# lfovca-rev3.net
KiCad netlist of a schematic drawn in EAGLE
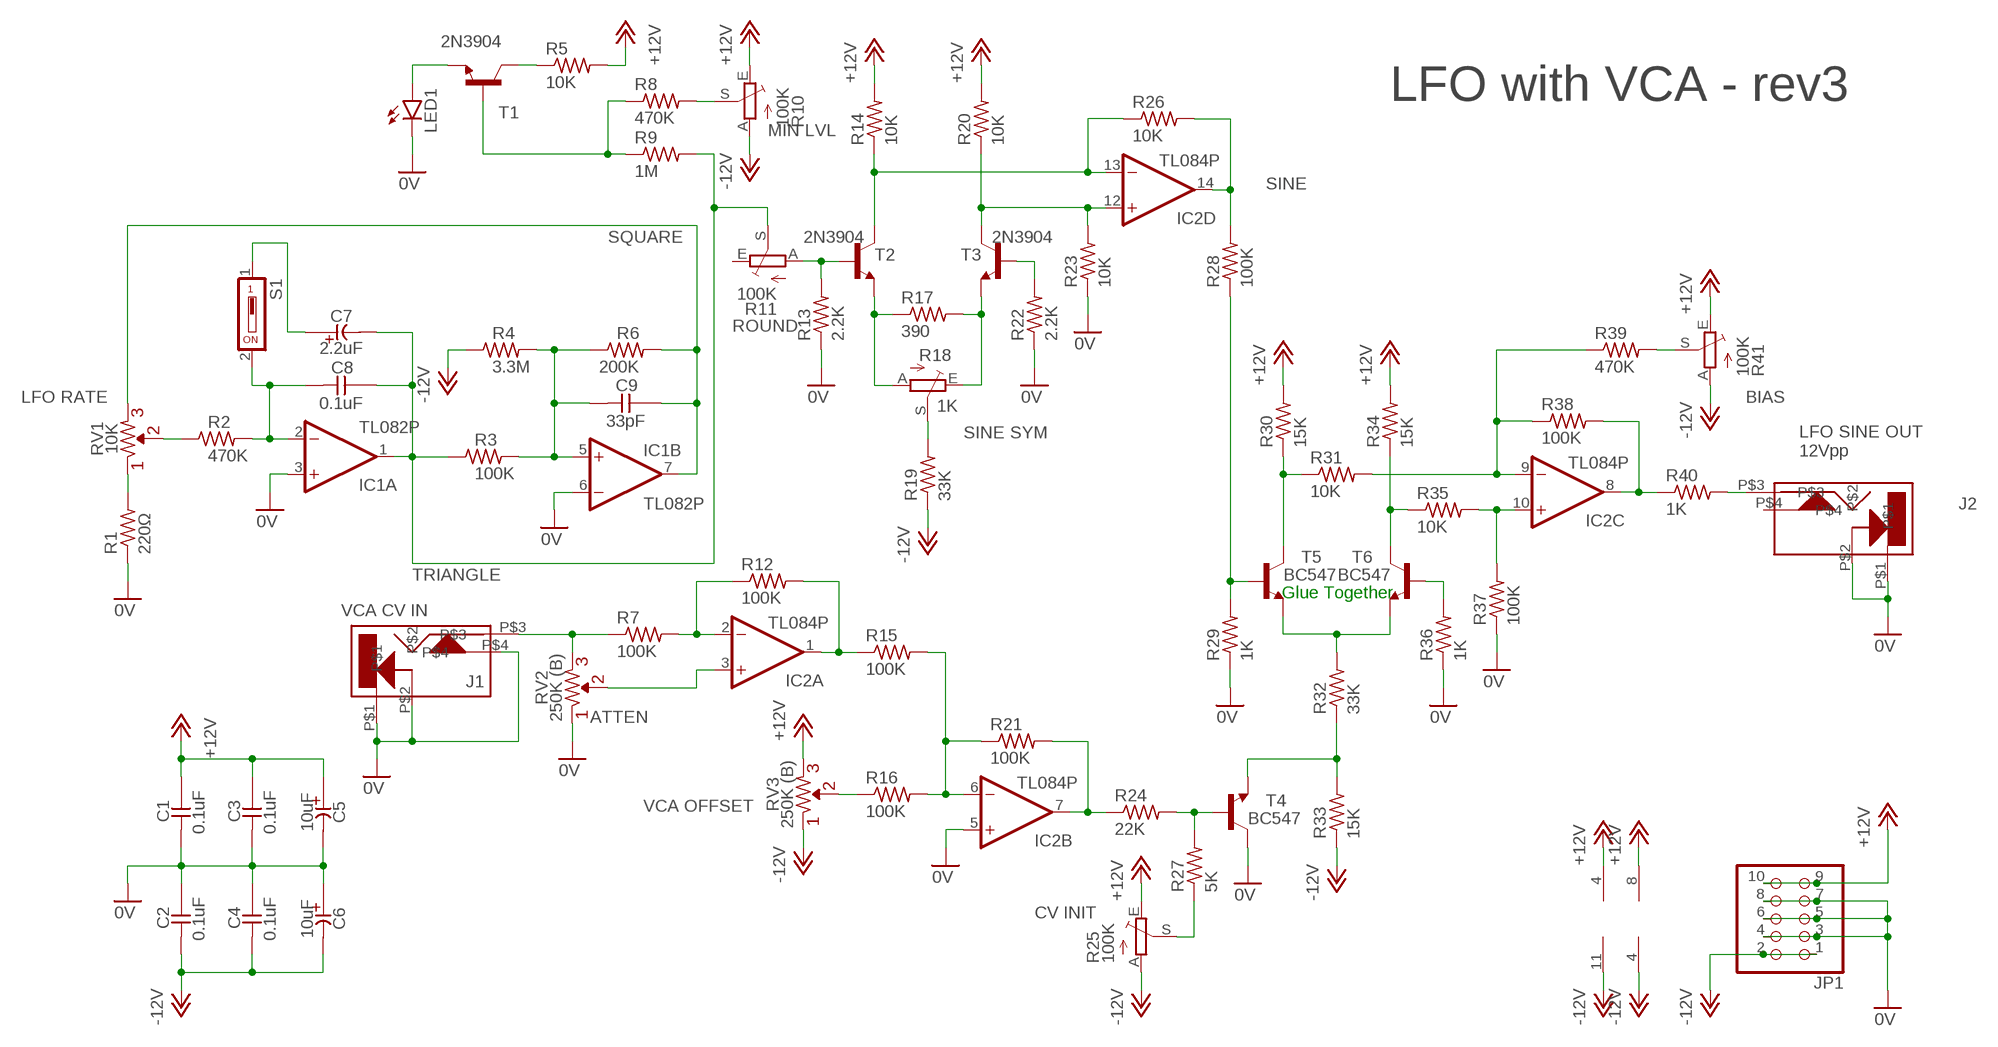
[diagram p0: schematic, sheet 1]

(export (version "E")
  (design (tool "Eeschema 10.0.6"))
  (components
    (comp (ref "C1")
      (value "0.1uF")
      (footprint "eagle-import:C025-024X044")
      (libsource (lib "eagle-import") (part "CC-US025-024X044"))
    )
    (comp (ref "C2")
      (value "0.1uF")
      (footprint "eagle-import:C025-024X044")
      (libsource (lib "eagle-import") (part "CC-US025-024X044"))
    )
    (comp (ref "C3")
      (value "0.1uF")
      (footprint "eagle-import:C025-024X044")
      (libsource (lib "eagle-import") (part "CC-US025-024X044"))
    )
    (comp (ref "C4")
      (value "0.1uF")
      (footprint "eagle-import:C025-024X044")
      (libsource (lib "eagle-import") (part "CC-US025-024X044"))
    )
    (comp (ref "C5")
      (value "10uF")
      (footprint "eagle-import:E2-5")
      (libsource (lib "eagle-import") (part "CE-USE2-5"))
    )
    (comp (ref "C6")
      (value "10uF")
      (footprint "eagle-import:E2-5")
      (libsource (lib "eagle-import") (part "CE-USE2-5"))
    )
    (comp (ref "C7")
      (value "2.2uF")
      (footprint "eagle-import:E2-5")
      (libsource (lib "eagle-import") (part "CE-USE2-5"))
    )
    (comp (ref "C8")
      (value "0.1uF")
      (footprint "eagle-import:C025-024X044")
      (libsource (lib "eagle-import") (part "CC-US025-024X044"))
    )
    (comp (ref "C9")
      (value "33pF")
      (footprint "eagle-import:C025-024X044")
      (libsource (lib "eagle-import") (part "CC-US025-024X044"))
    )
    (comp (ref "IC1")
      (value "TL082P")
      (footprint "eagle-import:DIL08")
      (libsource (lib "eagle-import") (part "TL082P"))
    )
    (comp (ref "IC2")
      (value "TL084P")
      (footprint "eagle-import:DIL14")
      (libsource (lib "eagle-import") (part "TL084P"))
    )
    (comp (ref "J1")
      (value "CL1384")
      (footprint "eagle-import:CL1384")
      (libsource (lib "eagle-import") (part "CL1384"))
    )
    (comp (ref "J2")
      (value "CL1384")
      (footprint "eagle-import:CL1384")
      (libsource (lib "eagle-import") (part "CL1384"))
    )
    (comp (ref "JP1")
      (value "PINHD-2X5")
      (footprint "eagle-import:2X05")
      (libsource (lib "eagle-import") (part "PINHD-2X5"))
    )
    (comp (ref "LED1")
      (value "LED3MM")
      (footprint "eagle-import:LED3MM")
      (libsource (lib "eagle-import") (part "LED3MM"))
    )
    (comp (ref "R1")
      (value "220Ω")
      (footprint "eagle-import:0207_7")
      (libsource (lib "eagle-import") (part "R-US_0207/7"))
    )
    (comp (ref "R2")
      (value "470K")
      (footprint "eagle-import:0207_7")
      (libsource (lib "eagle-import") (part "R-US_0207/7"))
    )
    (comp (ref "R3")
      (value "100K")
      (footprint "eagle-import:0207_7")
      (libsource (lib "eagle-import") (part "R-US_0207/7"))
    )
    (comp (ref "R4")
      (value "3.3M")
      (footprint "eagle-import:0207_7")
      (libsource (lib "eagle-import") (part "R-US_0207/7"))
    )
    (comp (ref "R5")
      (value "10K")
      (footprint "eagle-import:0207_7")
      (libsource (lib "eagle-import") (part "R-US_0207/7"))
    )
    (comp (ref "R6")
      (value "200K")
      (footprint "eagle-import:0207_7")
      (libsource (lib "eagle-import") (part "R-US_0207/7"))
    )
    (comp (ref "R7")
      (value "100K")
      (footprint "eagle-import:0207_7")
      (libsource (lib "eagle-import") (part "R-US_0207/7"))
    )
    (comp (ref "R8")
      (value "470K")
      (footprint "eagle-import:0207_7")
      (libsource (lib "eagle-import") (part "R-US_0207/7"))
    )
    (comp (ref "R9")
      (value "1M")
      (footprint "eagle-import:0207_7")
      (libsource (lib "eagle-import") (part "R-US_0207/7"))
    )
    (comp (ref "R10")
      (value "100K")
      (footprint "eagle-import:CA6V")
      (libsource (lib "eagle-import") (part "TRIM_EU-CA6V"))
    )
    (comp (ref "R11")
      (value "100K")
      (footprint "eagle-import:CA6V")
      (libsource (lib "eagle-import") (part "TRIM_EU-CA6V"))
    )
    (comp (ref "R12")
      (value "100K")
      (footprint "eagle-import:0207_7")
      (libsource (lib "eagle-import") (part "R-US_0207/7"))
    )
    (comp (ref "R13")
      (value "2.2K")
      (footprint "eagle-import:0207_7")
      (libsource (lib "eagle-import") (part "R-US_0207/7"))
    )
    (comp (ref "R14")
      (value "10K")
      (footprint "eagle-import:0207_7")
      (libsource (lib "eagle-import") (part "R-US_0207/7"))
    )
    (comp (ref "R15")
      (value "100K")
      (footprint "eagle-import:0207_7")
      (libsource (lib "eagle-import") (part "R-US_0207/7"))
    )
    (comp (ref "R16")
      (value "100K")
      (footprint "eagle-import:0207_7")
      (libsource (lib "eagle-import") (part "R-US_0207/7"))
    )
    (comp (ref "R17")
      (value "390")
      (footprint "eagle-import:0207_7")
      (libsource (lib "eagle-import") (part "R-US_0207/7"))
    )
    (comp (ref "R18")
      (value "1K")
      (footprint "eagle-import:CA6V")
      (libsource (lib "eagle-import") (part "TRIM_EU-CA6V"))
    )
    (comp (ref "R19")
      (value "33K")
      (footprint "eagle-import:0207_7")
      (libsource (lib "eagle-import") (part "R-US_0207/7"))
    )
    (comp (ref "R20")
      (value "10K")
      (footprint "eagle-import:0207_7")
      (libsource (lib "eagle-import") (part "R-US_0207/7"))
    )
    (comp (ref "R21")
      (value "100K")
      (footprint "eagle-import:0207_7")
      (libsource (lib "eagle-import") (part "R-US_0207/7"))
    )
    (comp (ref "R22")
      (value "2.2K")
      (footprint "eagle-import:0207_7")
      (libsource (lib "eagle-import") (part "R-US_0207/7"))
    )
    (comp (ref "R23")
      (value "10K")
      (footprint "eagle-import:0207_7")
      (libsource (lib "eagle-import") (part "R-US_0207/7"))
    )
    (comp (ref "R24")
      (value "22K")
      (footprint "eagle-import:0207_7")
      (libsource (lib "eagle-import") (part "R-US_0207/7"))
    )
    (comp (ref "R25")
      (value "100K")
      (footprint "eagle-import:CA6V")
      (libsource (lib "eagle-import") (part "TRIM_EU-CA6V"))
    )
    (comp (ref "R26")
      (value "10K")
      (footprint "eagle-import:0207_7")
      (libsource (lib "eagle-import") (part "R-US_0207/7"))
    )
    (comp (ref "R27")
      (value "5K")
      (footprint "eagle-import:0207_7")
      (libsource (lib "eagle-import") (part "R-US_0207/7"))
    )
    (comp (ref "R28")
      (value "100K")
      (footprint "eagle-import:0207_7")
      (libsource (lib "eagle-import") (part "R-US_0207/7"))
    )
    (comp (ref "R29")
      (value "1K")
      (footprint "eagle-import:0207_7")
      (libsource (lib "eagle-import") (part "R-US_0207/7"))
    )
    (comp (ref "R30")
      (value "15K")
      (footprint "eagle-import:0207_7")
      (libsource (lib "eagle-import") (part "R-US_0207/7"))
    )
    (comp (ref "R31")
      (value "10K")
      (footprint "eagle-import:0207_7")
      (libsource (lib "eagle-import") (part "R-US_0207/7"))
    )
    (comp (ref "R32")
      (value "33K")
      (footprint "eagle-import:0207_7")
      (libsource (lib "eagle-import") (part "R-US_0207/7"))
    )
    (comp (ref "R33")
      (value "15K")
      (footprint "eagle-import:0207_7")
      (libsource (lib "eagle-import") (part "R-US_0207/7"))
    )
    (comp (ref "R34")
      (value "15K")
      (footprint "eagle-import:0207_7")
      (libsource (lib "eagle-import") (part "R-US_0207/7"))
    )
    (comp (ref "R35")
      (value "10K")
      (footprint "eagle-import:0207_7")
      (libsource (lib "eagle-import") (part "R-US_0207/7"))
    )
    (comp (ref "R36")
      (value "1K")
      (footprint "eagle-import:0207_7")
      (libsource (lib "eagle-import") (part "R-US_0207/7"))
    )
    (comp (ref "R37")
      (value "100K")
      (footprint "eagle-import:0207_7")
      (libsource (lib "eagle-import") (part "R-US_0207/7"))
    )
    (comp (ref "R38")
      (value "100K")
      (footprint "eagle-import:0207_7")
      (libsource (lib "eagle-import") (part "R-US_0207/7"))
    )
    (comp (ref "R39")
      (value "470K")
      (footprint "eagle-import:0207_7")
      (libsource (lib "eagle-import") (part "R-US_0207/7"))
    )
    (comp (ref "R40")
      (value "1K")
      (footprint "eagle-import:0207_7")
      (libsource (lib "eagle-import") (part "R-US_0207/7"))
    )
    (comp (ref "R41")
      (value "100K")
      (footprint "eagle-import:CA6V")
      (libsource (lib "eagle-import") (part "TRIM_EU-CA6V"))
    )
    (comp (ref "RV1")
      (value "10K")
      (footprint "eagle-import:_COMMON_3RP_1610N")
      (libsource (lib "eagle-import") (part "R-VARR-VAR-10"))
    )
    (comp (ref "RV2")
      (value "250K (B)")
      (footprint "eagle-import:_COMMON_3RP_1610N")
      (libsource (lib "eagle-import") (part "R-VARR-VAR-10"))
    )
    (comp (ref "RV3")
      (value "250K (B)")
      (footprint "eagle-import:_COMMON_3RP_1610N")
      (libsource (lib "eagle-import") (part "R-VARR-VAR-10"))
    )
    (comp (ref "S1")
      (value "DS01")
      (footprint "eagle-import:DS-01")
      (libsource (lib "eagle-import") (part "DS01"))
    )
    (comp (ref "T1")
      (value "2N3904")
      (footprint "eagle-import:TO92-EBC")
      (libsource (lib "eagle-import") (part "-NPN-TO92-EBC2N3904"))
    )
    (comp (ref "T2")
      (value "2N3904")
      (footprint "eagle-import:TO92-EBC")
      (libsource (lib "eagle-import") (part "-NPN-TO92-EBC2N3904"))
    )
    (comp (ref "T3")
      (value "2N3904")
      (footprint "eagle-import:TO92-EBC")
      (libsource (lib "eagle-import") (part "-NPN-TO92-EBC2N3904"))
    )
    (comp (ref "T4")
      (value "BC547")
      (footprint "eagle-import:TO92-CBE")
      (libsource (lib "eagle-import") (part "-NPN-TO92-CBEBC547"))
    )
    (comp (ref "T5")
      (value "BC547")
      (footprint "eagle-import:TO92-CBE")
      (libsource (lib "eagle-import") (part "-NPN-TO92-CBEBC547"))
    )
    (comp (ref "T6")
      (value "BC547")
      (footprint "eagle-import:TO92-CBE")
      (libsource (lib "eagle-import") (part "-NPN-TO92-CBEBC547"))
    )
  )
  (nets
    (net (code "1") (name "+12V") (class "Default")
      (node (ref "C1") (pin "1") (pinfunction "1_1") (pintype "passive"))
      (node (ref "C3") (pin "1") (pinfunction "1_1") (pintype "passive"))
      (node (ref "C5") (pin "+") (pinfunction "+_+") (pintype "passive"))
      (node (ref "IC1") (pin "8") (pinfunction "V+_8") (pintype "power_in"))
      (node (ref "IC2") (pin "4") (pinfunction "V+_4") (pintype "power_in"))
      (node (ref "JP1") (pin "10") (pinfunction "10_10") (pintype "passive"))
      (node (ref "JP1") (pin "9") (pinfunction "9_9") (pintype "passive"))
      (node (ref "R10") (pin "E") (pinfunction "E_E") (pintype "passive"))
      (node (ref "R14") (pin "2") (pinfunction "2_2") (pintype "passive"))
      (node (ref "R20") (pin "2") (pinfunction "2_2") (pintype "passive"))
      (node (ref "R25") (pin "E") (pinfunction "E_E") (pintype "passive"))
      (node (ref "R30") (pin "2") (pinfunction "2_2") (pintype "passive"))
      (node (ref "R34") (pin "2") (pinfunction "2_2") (pintype "passive"))
      (node (ref "R41") (pin "E") (pinfunction "E_E") (pintype "passive"))
      (node (ref "R5") (pin "2") (pinfunction "2_2") (pintype "passive"))
      (node (ref "RV3") (pin "3") (pinfunction "3_3") (pintype "passive"))
    )
    (net (code "2") (name "-12V") (class "Default")
      (node (ref "C2") (pin "2") (pinfunction "2_2") (pintype "passive"))
      (node (ref "C4") (pin "2") (pinfunction "2_2") (pintype "passive"))
      (node (ref "C6") (pin "-") (pinfunction "-_-") (pintype "passive"))
      (node (ref "IC1") (pin "4") (pinfunction "V-_4") (pintype "power_in"))
      (node (ref "IC2") (pin "11") (pinfunction "V-_11") (pintype "power_in"))
      (node (ref "JP1") (pin "1") (pinfunction "1_1") (pintype "passive"))
      (node (ref "JP1") (pin "2") (pinfunction "2_2") (pintype "passive"))
      (node (ref "R10") (pin "A") (pinfunction "A_A") (pintype "passive"))
      (node (ref "R19") (pin "1") (pinfunction "1_1") (pintype "passive"))
      (node (ref "R25") (pin "A") (pinfunction "A_A") (pintype "passive"))
      (node (ref "R33") (pin "1") (pinfunction "1_1") (pintype "passive"))
      (node (ref "R4") (pin "1") (pinfunction "1_1") (pintype "passive"))
      (node (ref "R41") (pin "A") (pinfunction "A_A") (pintype "passive"))
      (node (ref "RV3") (pin "1") (pinfunction "1_1") (pintype "passive"))
    )
    (net (code "3") (name "0V") (class "Default")
      (node (ref "C1") (pin "2") (pinfunction "2_2") (pintype "passive"))
      (node (ref "C2") (pin "1") (pinfunction "1_1") (pintype "passive"))
      (node (ref "C3") (pin "2") (pinfunction "2_2") (pintype "passive"))
      (node (ref "C4") (pin "1") (pinfunction "1_1") (pintype "passive"))
      (node (ref "C5") (pin "-") (pinfunction "-_-") (pintype "passive"))
      (node (ref "C6") (pin "+") (pinfunction "+_+") (pintype "passive"))
      (node (ref "IC1") (pin "3") (pinfunction "+IN_3") (pintype "input"))
      (node (ref "IC1") (pin "6") (pinfunction "-IN_6") (pintype "input"))
      (node (ref "IC2") (pin "5") (pinfunction "+IN_5") (pintype "input"))
      (node (ref "J1") (pin "P$1") (pinfunction "P$1_P$1") (pintype "bidirectional"))
      (node (ref "J1") (pin "P$2") (pinfunction "P$2_P$2") (pintype "bidirectional"))
      (node (ref "J1") (pin "P$4") (pinfunction "P$4_P$4") (pintype "bidirectional"))
      (node (ref "J2") (pin "P$1") (pinfunction "P$1_P$1") (pintype "bidirectional"))
      (node (ref "J2") (pin "P$2") (pinfunction "P$2_P$2") (pintype "bidirectional"))
      (node (ref "JP1") (pin "3") (pinfunction "3_3") (pintype "passive"))
      (node (ref "JP1") (pin "4") (pinfunction "4_4") (pintype "passive"))
      (node (ref "JP1") (pin "5") (pinfunction "5_5") (pintype "passive"))
      (node (ref "JP1") (pin "6") (pinfunction "6_6") (pintype "passive"))
      (node (ref "JP1") (pin "7") (pinfunction "7_7") (pintype "passive"))
      (node (ref "JP1") (pin "8") (pinfunction "8_8") (pintype "passive"))
      (node (ref "LED1") (pin "K") (pinfunction "C_K") (pintype "passive"))
      (node (ref "R1") (pin "1") (pinfunction "1_1") (pintype "passive"))
      (node (ref "R13") (pin "1") (pinfunction "1_1") (pintype "passive"))
      (node (ref "R22") (pin "1") (pinfunction "1_1") (pintype "passive"))
      (node (ref "R23") (pin "1") (pinfunction "1_1") (pintype "passive"))
      (node (ref "R29") (pin "1") (pinfunction "1_1") (pintype "passive"))
      (node (ref "R36") (pin "1") (pinfunction "1_1") (pintype "passive"))
      (node (ref "R37") (pin "1") (pinfunction "1_1") (pintype "passive"))
      (node (ref "RV2") (pin "1") (pinfunction "1_1") (pintype "passive"))
      (node (ref "T4") (pin "C") (pinfunction "C_C") (pintype "passive"))
    )
    (net (code "4") (name "Net-(C7-Pad+)") (class "Default")
      (node (ref "C7") (pin "+") (pinfunction "+_+") (pintype "passive"))
      (node (ref "S1") (pin "1") (pinfunction "1_1") (pintype "passive"))
    )
    (net (code "5") (name "Net-(IC1A--IN)") (class "Default")
      (node (ref "C8") (pin "2") (pinfunction "2_2") (pintype "passive"))
      (node (ref "IC1") (pin "2") (pinfunction "-IN_2") (pintype "input"))
      (node (ref "R2") (pin "2") (pinfunction "2_2") (pintype "passive"))
      (node (ref "S1") (pin "2") (pinfunction "2_2") (pintype "passive"))
    )
    (net (code "6") (name "Net-(IC1A-OUT)") (class "Default")
      (node (ref "C7") (pin "-") (pinfunction "-_-") (pintype "passive"))
      (node (ref "C8") (pin "1") (pinfunction "1_1") (pintype "passive"))
      (node (ref "IC1") (pin "1") (pinfunction "OUT_1") (pintype "output"))
      (node (ref "R11") (pin "S") (pinfunction "S_S") (pintype "passive"))
      (node (ref "R3") (pin "1") (pinfunction "1_1") (pintype "passive"))
      (node (ref "R9") (pin "2") (pinfunction "2_2") (pintype "passive"))
    )
    (net (code "7") (name "Net-(IC1B-+IN)") (class "Default")
      (node (ref "C9") (pin "2") (pinfunction "2_2") (pintype "passive"))
      (node (ref "IC1") (pin "5") (pinfunction "+IN_5") (pintype "input"))
      (node (ref "R3") (pin "2") (pinfunction "2_2") (pintype "passive"))
      (node (ref "R4") (pin "2") (pinfunction "2_2") (pintype "passive"))
      (node (ref "R6") (pin "1") (pinfunction "1_1") (pintype "passive"))
    )
    (net (code "8") (name "Net-(IC1B-OUT)") (class "Default")
      (node (ref "C9") (pin "1") (pinfunction "1_1") (pintype "passive"))
      (node (ref "IC1") (pin "7") (pinfunction "OUT_7") (pintype "output"))
      (node (ref "R6") (pin "2") (pinfunction "2_2") (pintype "passive"))
      (node (ref "RV1") (pin "3") (pinfunction "3_3") (pintype "passive"))
    )
    (net (code "9") (name "Net-(IC2A-+IN)") (class "Default")
      (node (ref "IC2") (pin "3") (pinfunction "+IN_3") (pintype "input"))
      (node (ref "RV2") (pin "2") (pinfunction "2_2") (pintype "passive"))
    )
    (net (code "10") (name "Net-(IC2A--IN)") (class "Default")
      (node (ref "IC2") (pin "2") (pinfunction "-IN_2") (pintype "input"))
      (node (ref "R12") (pin "1") (pinfunction "1_1") (pintype "passive"))
      (node (ref "R7") (pin "2") (pinfunction "2_2") (pintype "passive"))
    )
    (net (code "11") (name "Net-(IC2A-OUT)") (class "Default")
      (node (ref "IC2") (pin "1") (pinfunction "OUT_1") (pintype "output"))
      (node (ref "R12") (pin "2") (pinfunction "2_2") (pintype "passive"))
      (node (ref "R15") (pin "1") (pinfunction "1_1") (pintype "passive"))
    )
    (net (code "12") (name "Net-(IC2B--IN)") (class "Default")
      (node (ref "IC2") (pin "6") (pinfunction "-IN_6") (pintype "input"))
      (node (ref "R15") (pin "2") (pinfunction "2_2") (pintype "passive"))
      (node (ref "R16") (pin "2") (pinfunction "2_2") (pintype "passive"))
      (node (ref "R21") (pin "1") (pinfunction "1_1") (pintype "passive"))
    )
    (net (code "13") (name "Net-(IC2B-OUT)") (class "Default")
      (node (ref "IC2") (pin "7") (pinfunction "OUT_7") (pintype "output"))
      (node (ref "R21") (pin "2") (pinfunction "2_2") (pintype "passive"))
      (node (ref "R24") (pin "1") (pinfunction "1_1") (pintype "passive"))
    )
    (net (code "14") (name "Net-(IC2C-+IN)") (class "Default")
      (node (ref "IC2") (pin "10") (pinfunction "+IN_10") (pintype "input"))
      (node (ref "R35") (pin "2") (pinfunction "2_2") (pintype "passive"))
      (node (ref "R37") (pin "2") (pinfunction "2_2") (pintype "passive"))
    )
    (net (code "15") (name "Net-(IC2C--IN)") (class "Default")
      (node (ref "IC2") (pin "9") (pinfunction "-IN_9") (pintype "input"))
      (node (ref "R31") (pin "2") (pinfunction "2_2") (pintype "passive"))
      (node (ref "R38") (pin "1") (pinfunction "1_1") (pintype "passive"))
      (node (ref "R39") (pin "1") (pinfunction "1_1") (pintype "passive"))
    )
    (net (code "16") (name "Net-(IC2C-OUT)") (class "Default")
      (node (ref "IC2") (pin "8") (pinfunction "OUT_8") (pintype "output"))
      (node (ref "R38") (pin "2") (pinfunction "2_2") (pintype "passive"))
      (node (ref "R40") (pin "1") (pinfunction "1_1") (pintype "passive"))
    )
    (net (code "17") (name "Net-(IC2D-+IN)") (class "Default")
      (node (ref "IC2") (pin "12") (pinfunction "+IN_12") (pintype "input"))
      (node (ref "R20") (pin "1") (pinfunction "1_1") (pintype "passive"))
      (node (ref "R23") (pin "2") (pinfunction "2_2") (pintype "passive"))
      (node (ref "T3") (pin "C") (pinfunction "C_C") (pintype "passive"))
    )
    (net (code "18") (name "Net-(IC2D--IN)") (class "Default")
      (node (ref "IC2") (pin "13") (pinfunction "-IN_13") (pintype "input"))
      (node (ref "R14") (pin "1") (pinfunction "1_1") (pintype "passive"))
      (node (ref "R26") (pin "1") (pinfunction "1_1") (pintype "passive"))
      (node (ref "T2") (pin "C") (pinfunction "C_C") (pintype "passive"))
    )
    (net (code "19") (name "Net-(IC2D-OUT)") (class "Default")
      (node (ref "IC2") (pin "14") (pinfunction "OUT_14") (pintype "output"))
      (node (ref "R26") (pin "2") (pinfunction "2_2") (pintype "passive"))
      (node (ref "R28") (pin "2") (pinfunction "2_2") (pintype "passive"))
    )
    (net (code "20") (name "Net-(J1-PadP$3)") (class "Default")
      (node (ref "J1") (pin "P$3") (pinfunction "P$3_P$3") (pintype "bidirectional"))
      (node (ref "R7") (pin "1") (pinfunction "1_1") (pintype "passive"))
      (node (ref "RV2") (pin "3") (pinfunction "3_3") (pintype "passive"))
    )
    (net (code "21") (name "Net-(J2-PadP$3)") (class "Default")
      (node (ref "J2") (pin "P$3") (pinfunction "P$3_P$3") (pintype "bidirectional"))
      (node (ref "R40") (pin "2") (pinfunction "2_2") (pintype "passive"))
    )
    (net (code "22") (name "Net-(LED1-PadA)") (class "Default")
      (node (ref "LED1") (pin "A") (pinfunction "A_A") (pintype "passive"))
      (node (ref "T1") (pin "E") (pinfunction "E_E") (pintype "passive"))
    )
    (net (code "23") (name "Net-(R1-Pad2)") (class "Default")
      (node (ref "R1") (pin "2") (pinfunction "2_2") (pintype "passive"))
      (node (ref "RV1") (pin "1") (pinfunction "1_1") (pintype "passive"))
    )
    (net (code "24") (name "Net-(R2-Pad1)") (class "Default")
      (node (ref "R2") (pin "1") (pinfunction "1_1") (pintype "passive"))
      (node (ref "RV1") (pin "2") (pinfunction "2_2") (pintype "passive"))
    )
    (net (code "25") (name "Net-(R5-Pad1)") (class "Default")
      (node (ref "R5") (pin "1") (pinfunction "1_1") (pintype "passive"))
      (node (ref "T1") (pin "C") (pinfunction "C_C") (pintype "passive"))
    )
    (net (code "26") (name "Net-(R8-Pad1)") (class "Default")
      (node (ref "R8") (pin "1") (pinfunction "1_1") (pintype "passive"))
      (node (ref "R9") (pin "1") (pinfunction "1_1") (pintype "passive"))
      (node (ref "T1") (pin "B") (pinfunction "B_B") (pintype "passive"))
    )
    (net (code "27") (name "Net-(R10-PadS)") (class "Default")
      (node (ref "R10") (pin "S") (pinfunction "S_S") (pintype "passive"))
      (node (ref "R8") (pin "2") (pinfunction "2_2") (pintype "passive"))
    )
    (net (code "28") (name "Net-(R11-PadA)") (class "Default")
      (node (ref "R11") (pin "A") (pinfunction "A_A") (pintype "passive"))
      (node (ref "R13") (pin "2") (pinfunction "2_2") (pintype "passive"))
      (node (ref "T2") (pin "B") (pinfunction "B_B") (pintype "passive"))
    )
    (net (code "29") (name "Net-(R16-Pad1)") (class "Default")
      (node (ref "R16") (pin "1") (pinfunction "1_1") (pintype "passive"))
      (node (ref "RV3") (pin "2") (pinfunction "2_2") (pintype "passive"))
    )
    (net (code "30") (name "Net-(R17-Pad1)") (class "Default")
      (node (ref "R17") (pin "1") (pinfunction "1_1") (pintype "passive"))
      (node (ref "R18") (pin "A") (pinfunction "A_A") (pintype "passive"))
      (node (ref "T2") (pin "E") (pinfunction "E_E") (pintype "passive"))
    )
    (net (code "31") (name "Net-(R17-Pad2)") (class "Default")
      (node (ref "R17") (pin "2") (pinfunction "2_2") (pintype "passive"))
      (node (ref "R18") (pin "E") (pinfunction "E_E") (pintype "passive"))
      (node (ref "T3") (pin "E") (pinfunction "E_E") (pintype "passive"))
    )
    (net (code "32") (name "Net-(R18-PadS)") (class "Default")
      (node (ref "R18") (pin "S") (pinfunction "S_S") (pintype "passive"))
      (node (ref "R19") (pin "2") (pinfunction "2_2") (pintype "passive"))
    )
    (net (code "33") (name "Net-(R22-Pad2)") (class "Default")
      (node (ref "R22") (pin "2") (pinfunction "2_2") (pintype "passive"))
      (node (ref "T3") (pin "B") (pinfunction "B_B") (pintype "passive"))
    )
    (net (code "34") (name "Net-(R24-Pad2)") (class "Default")
      (node (ref "R24") (pin "2") (pinfunction "2_2") (pintype "passive"))
      (node (ref "R27") (pin "2") (pinfunction "2_2") (pintype "passive"))
      (node (ref "T4") (pin "B") (pinfunction "B_B") (pintype "passive"))
    )
    (net (code "35") (name "Net-(R25-PadS)") (class "Default")
      (node (ref "R25") (pin "S") (pinfunction "S_S") (pintype "passive"))
      (node (ref "R27") (pin "1") (pinfunction "1_1") (pintype "passive"))
    )
    (net (code "36") (name "Net-(R28-Pad1)") (class "Default")
      (node (ref "R28") (pin "1") (pinfunction "1_1") (pintype "passive"))
      (node (ref "R29") (pin "2") (pinfunction "2_2") (pintype "passive"))
      (node (ref "T5") (pin "B") (pinfunction "B_B") (pintype "passive"))
    )
    (net (code "37") (name "Net-(R30-Pad1)") (class "Default")
      (node (ref "R30") (pin "1") (pinfunction "1_1") (pintype "passive"))
      (node (ref "R31") (pin "1") (pinfunction "1_1") (pintype "passive"))
      (node (ref "T5") (pin "C") (pinfunction "C_C") (pintype "passive"))
    )
    (net (code "38") (name "Net-(R32-Pad1)") (class "Default")
      (node (ref "R32") (pin "1") (pinfunction "1_1") (pintype "passive"))
      (node (ref "R33") (pin "2") (pinfunction "2_2") (pintype "passive"))
      (node (ref "T4") (pin "E") (pinfunction "E_E") (pintype "passive"))
    )
    (net (code "39") (name "Net-(R32-Pad2)") (class "Default")
      (node (ref "R32") (pin "2") (pinfunction "2_2") (pintype "passive"))
      (node (ref "T5") (pin "E") (pinfunction "E_E") (pintype "passive"))
      (node (ref "T6") (pin "E") (pinfunction "E_E") (pintype "passive"))
    )
    (net (code "40") (name "Net-(R34-Pad1)") (class "Default")
      (node (ref "R34") (pin "1") (pinfunction "1_1") (pintype "passive"))
      (node (ref "R35") (pin "1") (pinfunction "1_1") (pintype "passive"))
      (node (ref "T6") (pin "C") (pinfunction "C_C") (pintype "passive"))
    )
    (net (code "41") (name "Net-(R36-Pad2)") (class "Default")
      (node (ref "R36") (pin "2") (pinfunction "2_2") (pintype "passive"))
      (node (ref "T6") (pin "B") (pinfunction "B_B") (pintype "passive"))
    )
    (net (code "42") (name "Net-(R39-Pad2)") (class "Default")
      (node (ref "R39") (pin "2") (pinfunction "2_2") (pintype "passive"))
      (node (ref "R41") (pin "S") (pinfunction "S_S") (pintype "passive"))
    )
    (net (code "43") (name "unconnected-(J2-PadP$4)") (class "Default")
      (node (ref "J2") (pin "P$4") (pinfunction "P$4_P$4") (pintype "bidirectional"))
    )
    (net (code "44") (name "unconnected-(R11-PadE)") (class "Default")
      (node (ref "R11") (pin "E") (pinfunction "E_E") (pintype "passive"))
    )
  )
)
